# Cellphone-Detector-LM358-Flip-Flop.net
KiCad netlist of a schematic drawn in EAGLE
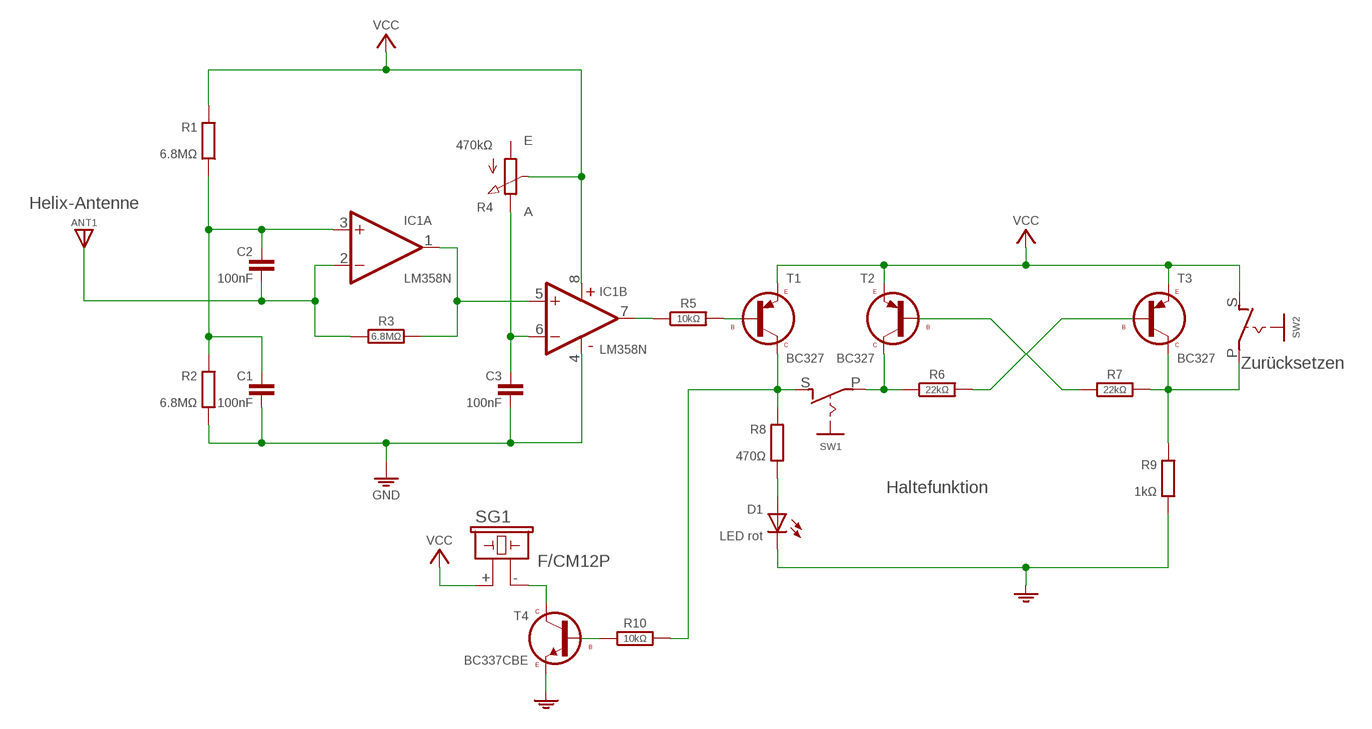
[diagram p0: schematic, sheet 1]

(export (version "E")
  (design (tool "Eeschema 10.0.6"))
  (components
    (comp (ref "ANT1")
      (value "ANT")
      (footprint "eagle-import:SPAD")
      (libsource (lib "eagle-import") (part "ANT"))
    )
    (comp (ref "C1")
      (value "100nF")
      (footprint "eagle-import:C050-025X060")
      (libsource (lib "eagle-import") (part "C025-025X060"))
    )
    (comp (ref "C2")
      (value "100nF")
      (footprint "eagle-import:C025-024X044")
      (libsource (lib "eagle-import") (part "C025-024X044"))
    )
    (comp (ref "C3")
      (value "100nF")
      (footprint "eagle-import:C025-024X044")
      (libsource (lib "eagle-import") (part "C025-024X044"))
    )
    (comp (ref "D1")
      (value "LED rot")
      (footprint "eagle-import:LED_3MM_V")
      (libsource (lib "eagle-import") (part "LED-3MM/V"))
    )
    (comp (ref "IC1")
      (value "LM358N")
      (footprint "eagle-import:DIL08")
      (libsource (lib "eagle-import") (part "LM358N"))
    )
    (comp (ref "R1")
      (value "6.8MΩ")
      (footprint "eagle-import:0204_2")
      (libsource (lib "eagle-import") (part "R0204/2"))
    )
    (comp (ref "R2")
      (value "6.8MΩ")
      (footprint "eagle-import:0204_2V")
      (libsource (lib "eagle-import") (part "R0204/2V"))
    )
    (comp (ref "R3")
      (value "6.8MΩ")
      (footprint "eagle-import:0202_2V")
      (libsource (lib "eagle-import") (part "R-H0202/2V"))
    )
    (comp (ref "R4")
      (value "470kΩ")
      (footprint "eagle-import:CONN-3P")
      (libsource (lib "eagle-import") (part "POT-3P"))
    )
    (comp (ref "R5")
      (value "10kΩ")
      (footprint "eagle-import:0204_10")
      (libsource (lib "eagle-import") (part "R-H0204/10"))
    )
    (comp (ref "R6")
      (value "22kΩ")
      (footprint "eagle-import:0204_10")
      (libsource (lib "eagle-import") (part "R-H0204/10"))
    )
    (comp (ref "R7")
      (value "22kΩ")
      (footprint "eagle-import:0204_10")
      (libsource (lib "eagle-import") (part "R-H0204/10"))
    )
    (comp (ref "R8")
      (value "470Ω")
      (footprint "eagle-import:0204_10-V")
      (libsource (lib "eagle-import") (part "R0204/10-V"))
    )
    (comp (ref "R9")
      (value "1kΩ")
      (footprint "eagle-import:0204_10")
      (libsource (lib "eagle-import") (part "R0204/10"))
    )
    (comp (ref "R10")
      (value "10kΩ")
      (footprint "eagle-import:0204_10")
      (libsource (lib "eagle-import") (part "R-H0204/10"))
    )
    (comp (ref "S1")
      (value "VCC_GNDR")
      (footprint "eagle-import:SPAD+-")
      (libsource (lib "eagle-import") (part "VCC_GNDR"))
    )
    (comp (ref "SG1")
      (value "F/CM12P")
      (footprint "eagle-import:F_CM12P")
      (libsource (lib "eagle-import") (part "F/CM12P"))
    )
    (comp (ref "SW1")
      (value "SW1")
      (footprint "eagle-import:SLSW-1P1T")
      (libsource (lib "eagle-import") (part "SL-SW-1P-1T"))
    )
    (comp (ref "SW2")
      (value "PB-1P-1T-2P")
      (footprint "eagle-import:SLSW-1P1T")
      (libsource (lib "eagle-import") (part "PB-1P-1T-2P"))
    )
    (comp (ref "T1")
      (value "BC327")
      (footprint "eagle-import:TO92")
      (libsource (lib "eagle-import") (part "BC327"))
    )
    (comp (ref "T2")
      (value "BC327")
      (footprint "eagle-import:TO92")
      (libsource (lib "eagle-import") (part "BC327"))
    )
    (comp (ref "T3")
      (value "BC327")
      (footprint "eagle-import:TO92")
      (libsource (lib "eagle-import") (part "BC327"))
    )
    (comp (ref "T4")
      (value "BC337CBE")
      (footprint "eagle-import:TO92-CBE")
      (libsource (lib "eagle-import") (part "BC337CBE"))
    )
  )
  (nets
    (net (code "1") (name "GND") (class "Default")
      (node (ref "C1") (pin "2") (pinfunction "2_2") (pintype "passive"))
      (node (ref "C3") (pin "2") (pinfunction "2_2") (pintype "passive"))
      (node (ref "D1") (pin "K") (pinfunction "C_K") (pintype "passive"))
      (node (ref "IC1") (pin "4") (pinfunction "V-_4") (pintype "power_in"))
      (node (ref "R2") (pin "2") (pinfunction "1_2") (pintype "passive"))
      (node (ref "R9") (pin "2") (pinfunction "1_2") (pintype "passive"))
      (node (ref "S1") (pin "1") (pinfunction "GND_1") (pintype "power_in"))
      (node (ref "T4") (pin "3") (pinfunction "E_3") (pintype "passive"))
    )
    (net (code "2") (name "Net-(IC1A-+IN)") (class "Default")
      (node (ref "C1") (pin "1") (pinfunction "1_1") (pintype "passive"))
      (node (ref "C2") (pin "1") (pinfunction "1_1") (pintype "passive"))
      (node (ref "IC1") (pin "3") (pinfunction "+IN_3") (pintype "input"))
      (node (ref "R1") (pin "2") (pinfunction "1_2") (pintype "passive"))
      (node (ref "R2") (pin "1") (pinfunction "2_1") (pintype "passive"))
    )
    (net (code "3") (name "Net-(IC1A--IN)") (class "Default")
      (node (ref "ANT1") (pin "1") (pinfunction "1_1") (pintype "output"))
      (node (ref "C2") (pin "2") (pinfunction "2_2") (pintype "passive"))
      (node (ref "IC1") (pin "2") (pinfunction "-IN_2") (pintype "input"))
      (node (ref "R3") (pin "1") (pinfunction "1_1") (pintype "passive"))
    )
    (net (code "4") (name "Net-(IC1A-OUT)") (class "Default")
      (node (ref "IC1") (pin "1") (pinfunction "OUT_1") (pintype "output"))
      (node (ref "IC1") (pin "5") (pinfunction "+IN_5") (pintype "input"))
      (node (ref "R3") (pin "2") (pinfunction "2_2") (pintype "passive"))
    )
    (net (code "5") (name "Net-(IC1B--IN)") (class "Default")
      (node (ref "C3") (pin "1") (pinfunction "1_1") (pintype "passive"))
      (node (ref "IC1") (pin "6") (pinfunction "-IN_6") (pintype "input"))
      (node (ref "R4") (pin "3") (pinfunction "E_3") (pintype "passive"))
    )
    (net (code "6") (name "Net-(IC1B-OUT)") (class "Default")
      (node (ref "IC1") (pin "7") (pinfunction "OUT_7") (pintype "output"))
      (node (ref "R5") (pin "1") (pinfunction "1_1") (pintype "passive"))
    )
    (net (code "7") (name "Net-(R8-1)") (class "Default")
      (node (ref "D1") (pin "A") (pinfunction "A_A") (pintype "passive"))
      (node (ref "R8") (pin "2") (pinfunction "1_2") (pintype "passive"))
    )
    (net (code "8") (name "Net-(R8-2)") (class "Default")
      (node (ref "R10") (pin "2") (pinfunction "2_2") (pintype "passive"))
      (node (ref "R8") (pin "1") (pinfunction "2_1") (pintype "passive"))
      (node (ref "SW1") (pin "S") (pinfunction "S_S") (pintype "passive"))
      (node (ref "T1") (pin "1") (pinfunction "C_1") (pintype "passive"))
    )
    (net (code "9") (name "Net-(R9-2)") (class "Default")
      (node (ref "R7") (pin "2") (pinfunction "2_2") (pintype "passive"))
      (node (ref "R9") (pin "1") (pinfunction "2_1") (pintype "passive"))
      (node (ref "SW2") (pin "P") (pinfunction "P_P") (pintype "passive"))
      (node (ref "T3") (pin "1") (pinfunction "C_1") (pintype "passive"))
    )
    (net (code "10") (name "Net-(SG1-2)") (class "Default")
      (node (ref "SG1") (pin "-") (pinfunction "2_-") (pintype "passive"))
      (node (ref "T4") (pin "1") (pinfunction "C_1") (pintype "passive"))
    )
    (net (code "11") (name "Net-(T1-B)") (class "Default")
      (node (ref "R5") (pin "2") (pinfunction "2_2") (pintype "passive"))
      (node (ref "T1") (pin "2") (pinfunction "B_2") (pintype "passive"))
    )
    (net (code "12") (name "Net-(T2-B)") (class "Default")
      (node (ref "R7") (pin "1") (pinfunction "1_1") (pintype "passive"))
      (node (ref "T2") (pin "2") (pinfunction "B_2") (pintype "passive"))
    )
    (net (code "13") (name "Net-(T2-C)") (class "Default")
      (node (ref "R6") (pin "1") (pinfunction "1_1") (pintype "passive"))
      (node (ref "SW1") (pin "P") (pinfunction "P_P") (pintype "passive"))
      (node (ref "T2") (pin "1") (pinfunction "C_1") (pintype "passive"))
    )
    (net (code "14") (name "Net-(T3-B)") (class "Default")
      (node (ref "R6") (pin "2") (pinfunction "2_2") (pintype "passive"))
      (node (ref "T3") (pin "2") (pinfunction "B_2") (pintype "passive"))
    )
    (net (code "15") (name "Net-(T4-B)") (class "Default")
      (node (ref "R10") (pin "1") (pinfunction "1_1") (pintype "passive"))
      (node (ref "T4") (pin "2") (pinfunction "B_2") (pintype "passive"))
    )
    (net (code "16") (name "VCC") (class "Default")
      (node (ref "IC1") (pin "8") (pinfunction "V+_8") (pintype "power_in"))
      (node (ref "R1") (pin "1") (pinfunction "2_1") (pintype "passive"))
      (node (ref "R4") (pin "2") (pinfunction "S_2") (pintype "passive"))
      (node (ref "S1") (pin "2") (pinfunction "VCC_2") (pintype "power_in"))
      (node (ref "SG1") (pin "+") (pinfunction "1_+") (pintype "passive"))
      (node (ref "SW2") (pin "S") (pinfunction "S_S") (pintype "passive"))
      (node (ref "T1") (pin "3") (pinfunction "E_3") (pintype "passive"))
      (node (ref "T2") (pin "3") (pinfunction "E_3") (pintype "passive"))
      (node (ref "T3") (pin "3") (pinfunction "E_3") (pintype "passive"))
    )
    (net (code "17") (name "unconnected-(R4-A-Pad1)") (class "Default")
      (node (ref "R4") (pin "1") (pinfunction "A_1") (pintype "passive"))
    )
  )
)
